# SCH_NFC-Business-Card_2024-06-08.net
KiCad netlist of a schematic drawn in EasyEDA
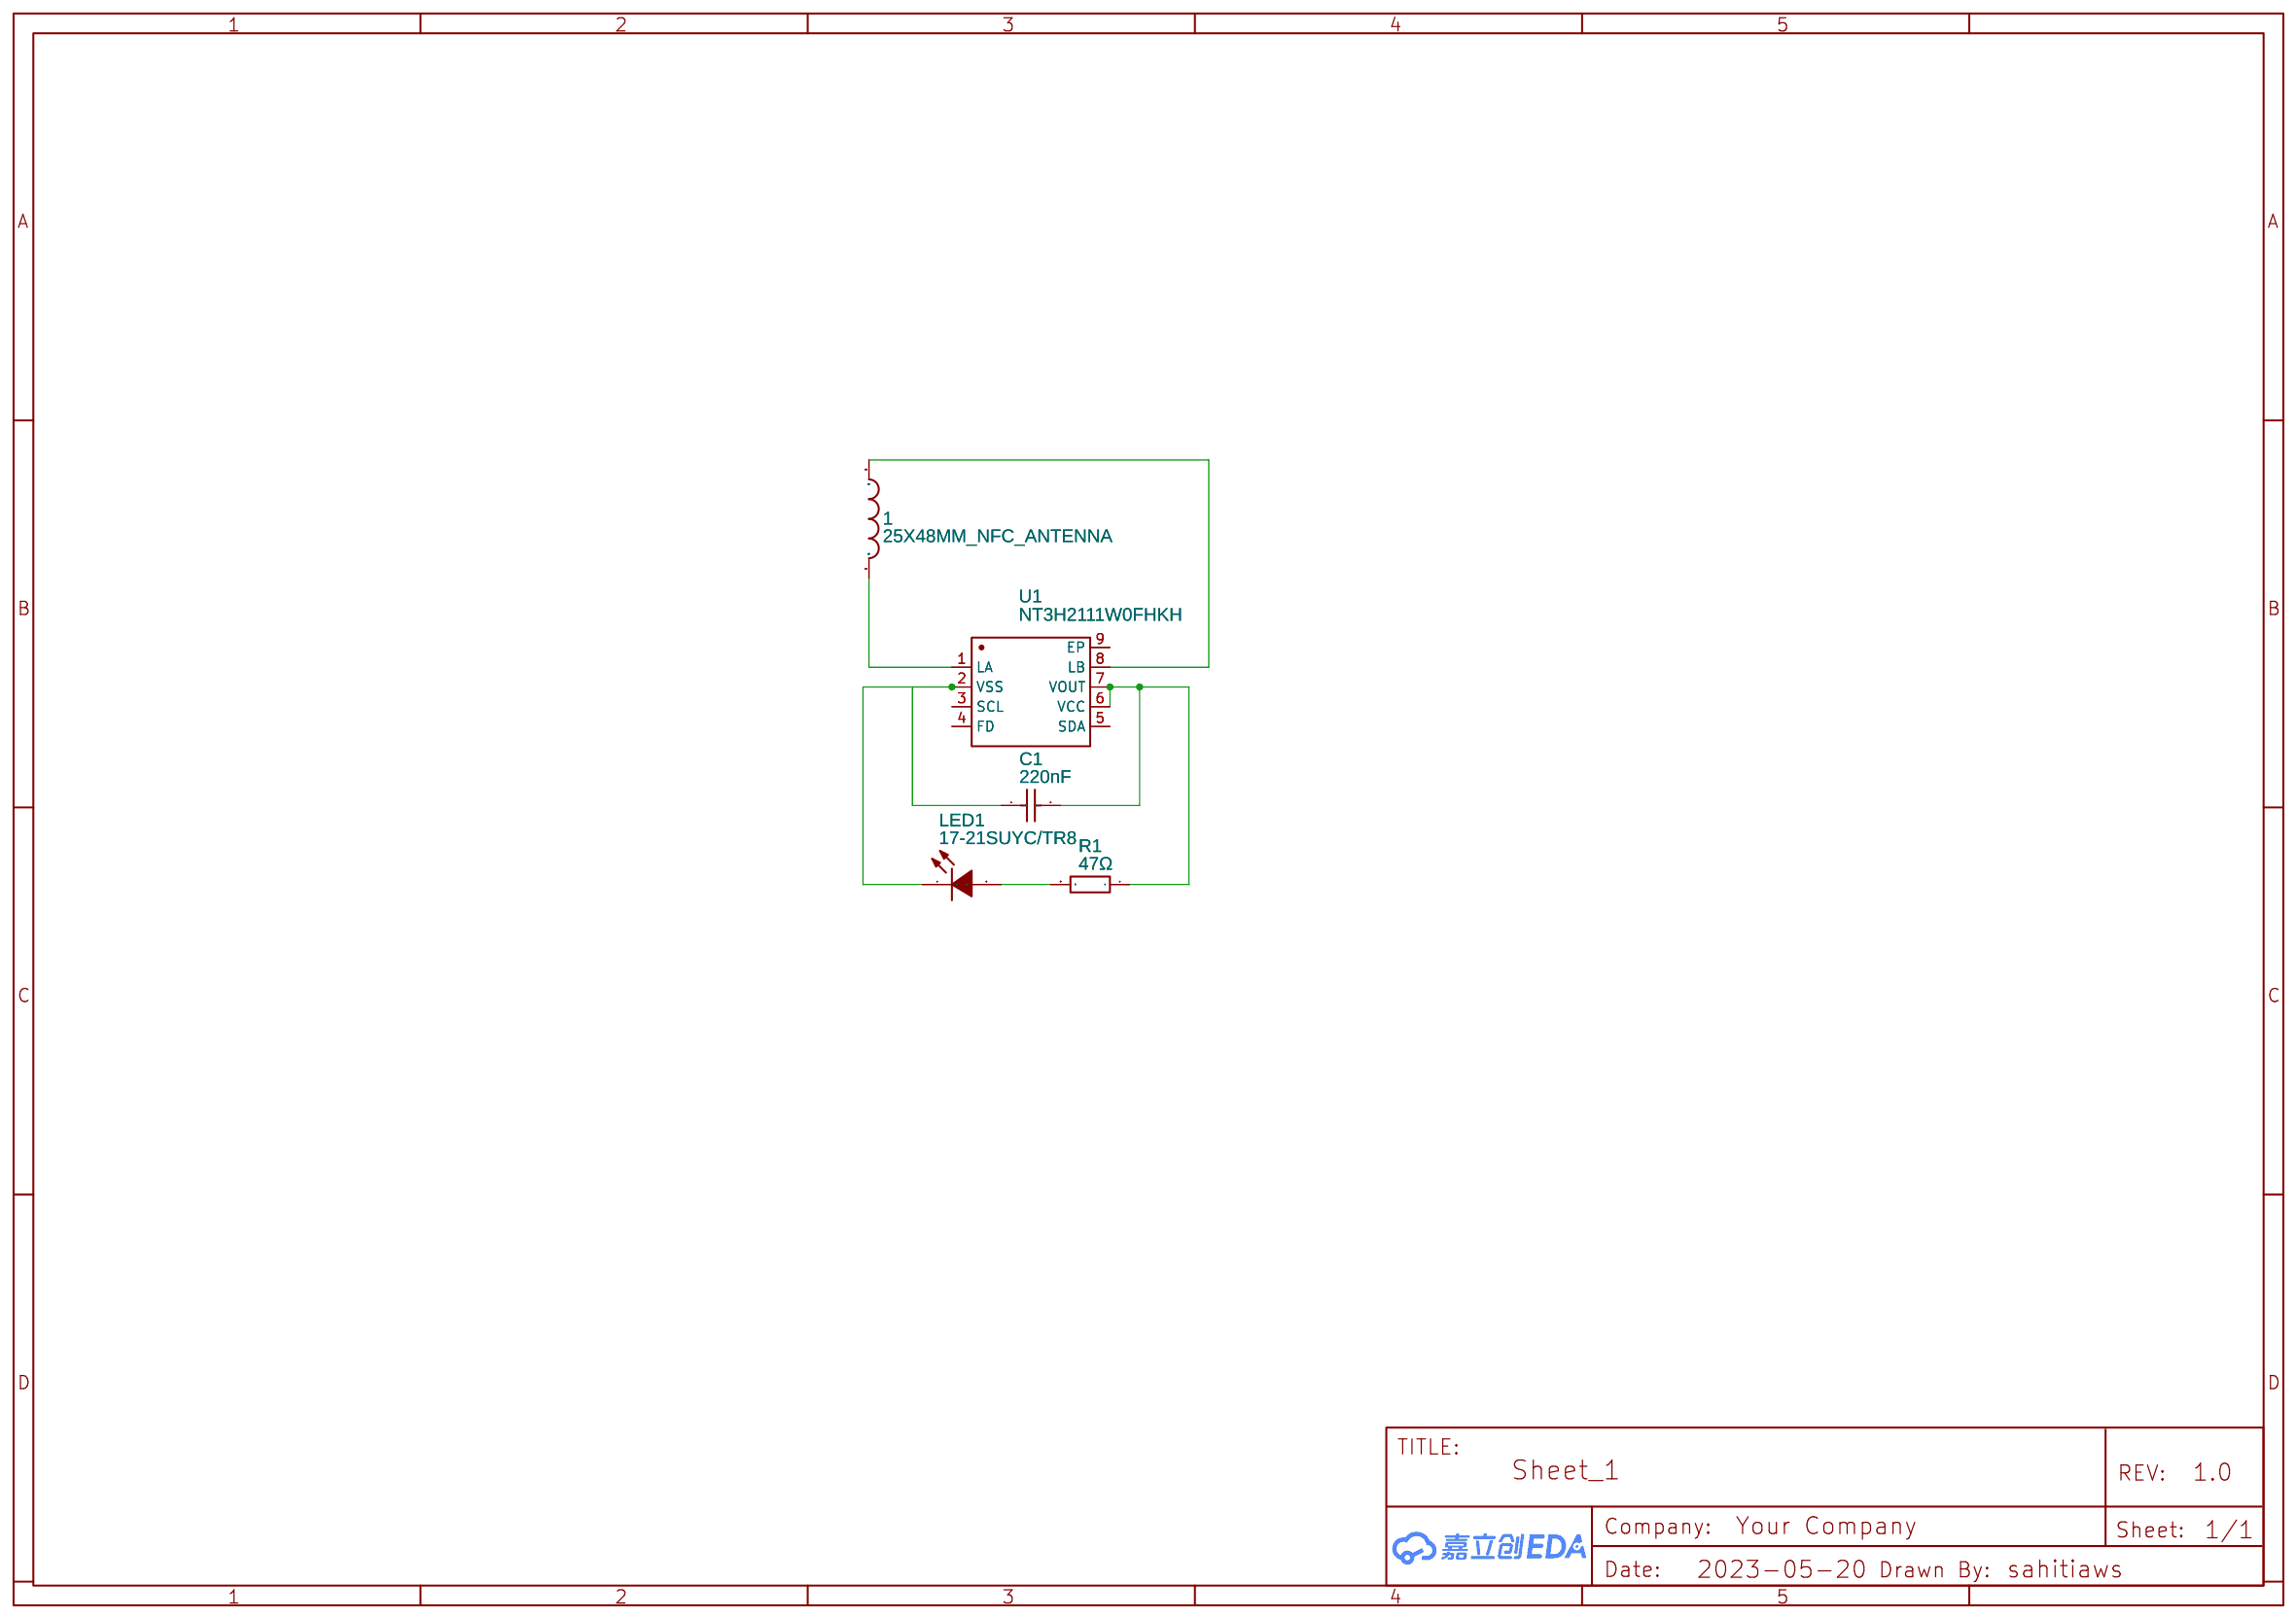
[diagram p0: schematic sheet]

(export (version "E")
  (design (tool "Eeschema 10.0.6"))
  (components
    (comp (ref "1") (value "25X48MM_NFC_ANTENNA") (libsource (lib "") (part "25X48MM_NFC_ANTENNA")))
    (comp (ref "C1")
      (value "220nF")
      (fields (field (name "Manufacturer Part") "CL10B224KA8NNNC") (field (name "Manufacturer") "SAMSUNG"))
      (libsource (lib "") (part "220N CL10B224KA8NNNC"))
    )
    (comp (ref "LED1")
      (value "17-21SUYC/TR8")
      (fields (field (name "Manufacturer") "KENTO"))
      (libsource (lib "") (part "17-21SUYC/TR8"))
    )
    (comp (ref "R1")
      (value "47Ω")
      (fields (field (name "Manufacturer Part") "0603WAF470JT5E") (field (name "Manufacturer") "UniOhm"))
      (libsource (lib "") (part "0603WAF470JT5E"))
    )
    (comp (ref "U1")
      (value "NT3H2111W0FHKH")
      (fields (field (name "Manufacturer") "NXP(恩智浦)"))
      (libsource (lib "") (part "NT3H2111W0FHKH"))
    )
  )
  (nets
    (net (code "1") (name "Net-(LED1-+)") (class "Default")
      (node (ref "LED1") (pin "2") (pinfunction "+_2") (pintype "unspecified"))
      (node (ref "R1") (pin "2") (pinfunction "2_2") (pintype "unspecified"))
    )
    (net (code "2") (name "Net-(LED1--)") (class "Default")
      (node (ref "C1") (pin "1") (pinfunction "1_1") (pintype "input"))
      (node (ref "LED1") (pin "1") (pinfunction "-_1") (pintype "unspecified"))
      (node (ref "U1") (pin "2") (pinfunction "VSS_2") (pintype "unspecified"))
    )
    (net (code "3") (name "Net-(U1-LA)") (class "Default")
      (node (ref "1") (pin "P$2") (pinfunction "P$2_P$2") (pintype "bidirectional"))
      (node (ref "U1") (pin "1") (pinfunction "LA_1") (pintype "unspecified"))
    )
    (net (code "4") (name "Net-(U1-LB)") (class "Default")
      (node (ref "1") (pin "P$1") (pinfunction "P$1_P$1") (pintype "bidirectional"))
      (node (ref "U1") (pin "8") (pinfunction "LB_8") (pintype "unspecified"))
    )
    (net (code "5") (name "Net-(U1-VCC)") (class "Default")
      (node (ref "C1") (pin "2") (pinfunction "2_2") (pintype "input"))
      (node (ref "R1") (pin "1") (pinfunction "1_1") (pintype "unspecified"))
      (node (ref "U1") (pin "6") (pinfunction "VCC_6") (pintype "unspecified"))
      (node (ref "U1") (pin "7") (pinfunction "VOUT_7") (pintype "unspecified"))
    )
    (net (code "6") (name "unconnected-(U1-EP-Pad9)") (class "Default")
      (node (ref "U1") (pin "9") (pinfunction "EP_9") (pintype "unspecified"))
    )
    (net (code "7") (name "unconnected-(U1-FD-Pad4)") (class "Default")
      (node (ref "U1") (pin "4") (pinfunction "FD_4") (pintype "unspecified"))
    )
    (net (code "8") (name "unconnected-(U1-SCL-Pad3)") (class "Default")
      (node (ref "U1") (pin "3") (pinfunction "SCL_3") (pintype "unspecified"))
    )
    (net (code "9") (name "unconnected-(U1-SDA-Pad5)") (class "Default")
      (node (ref "U1") (pin "5") (pinfunction "SDA_5") (pintype "unspecified"))
    )
  )
)
